# OpenPilot_Atom.net
KiCad netlist of a schematic drawn in Altium Designer
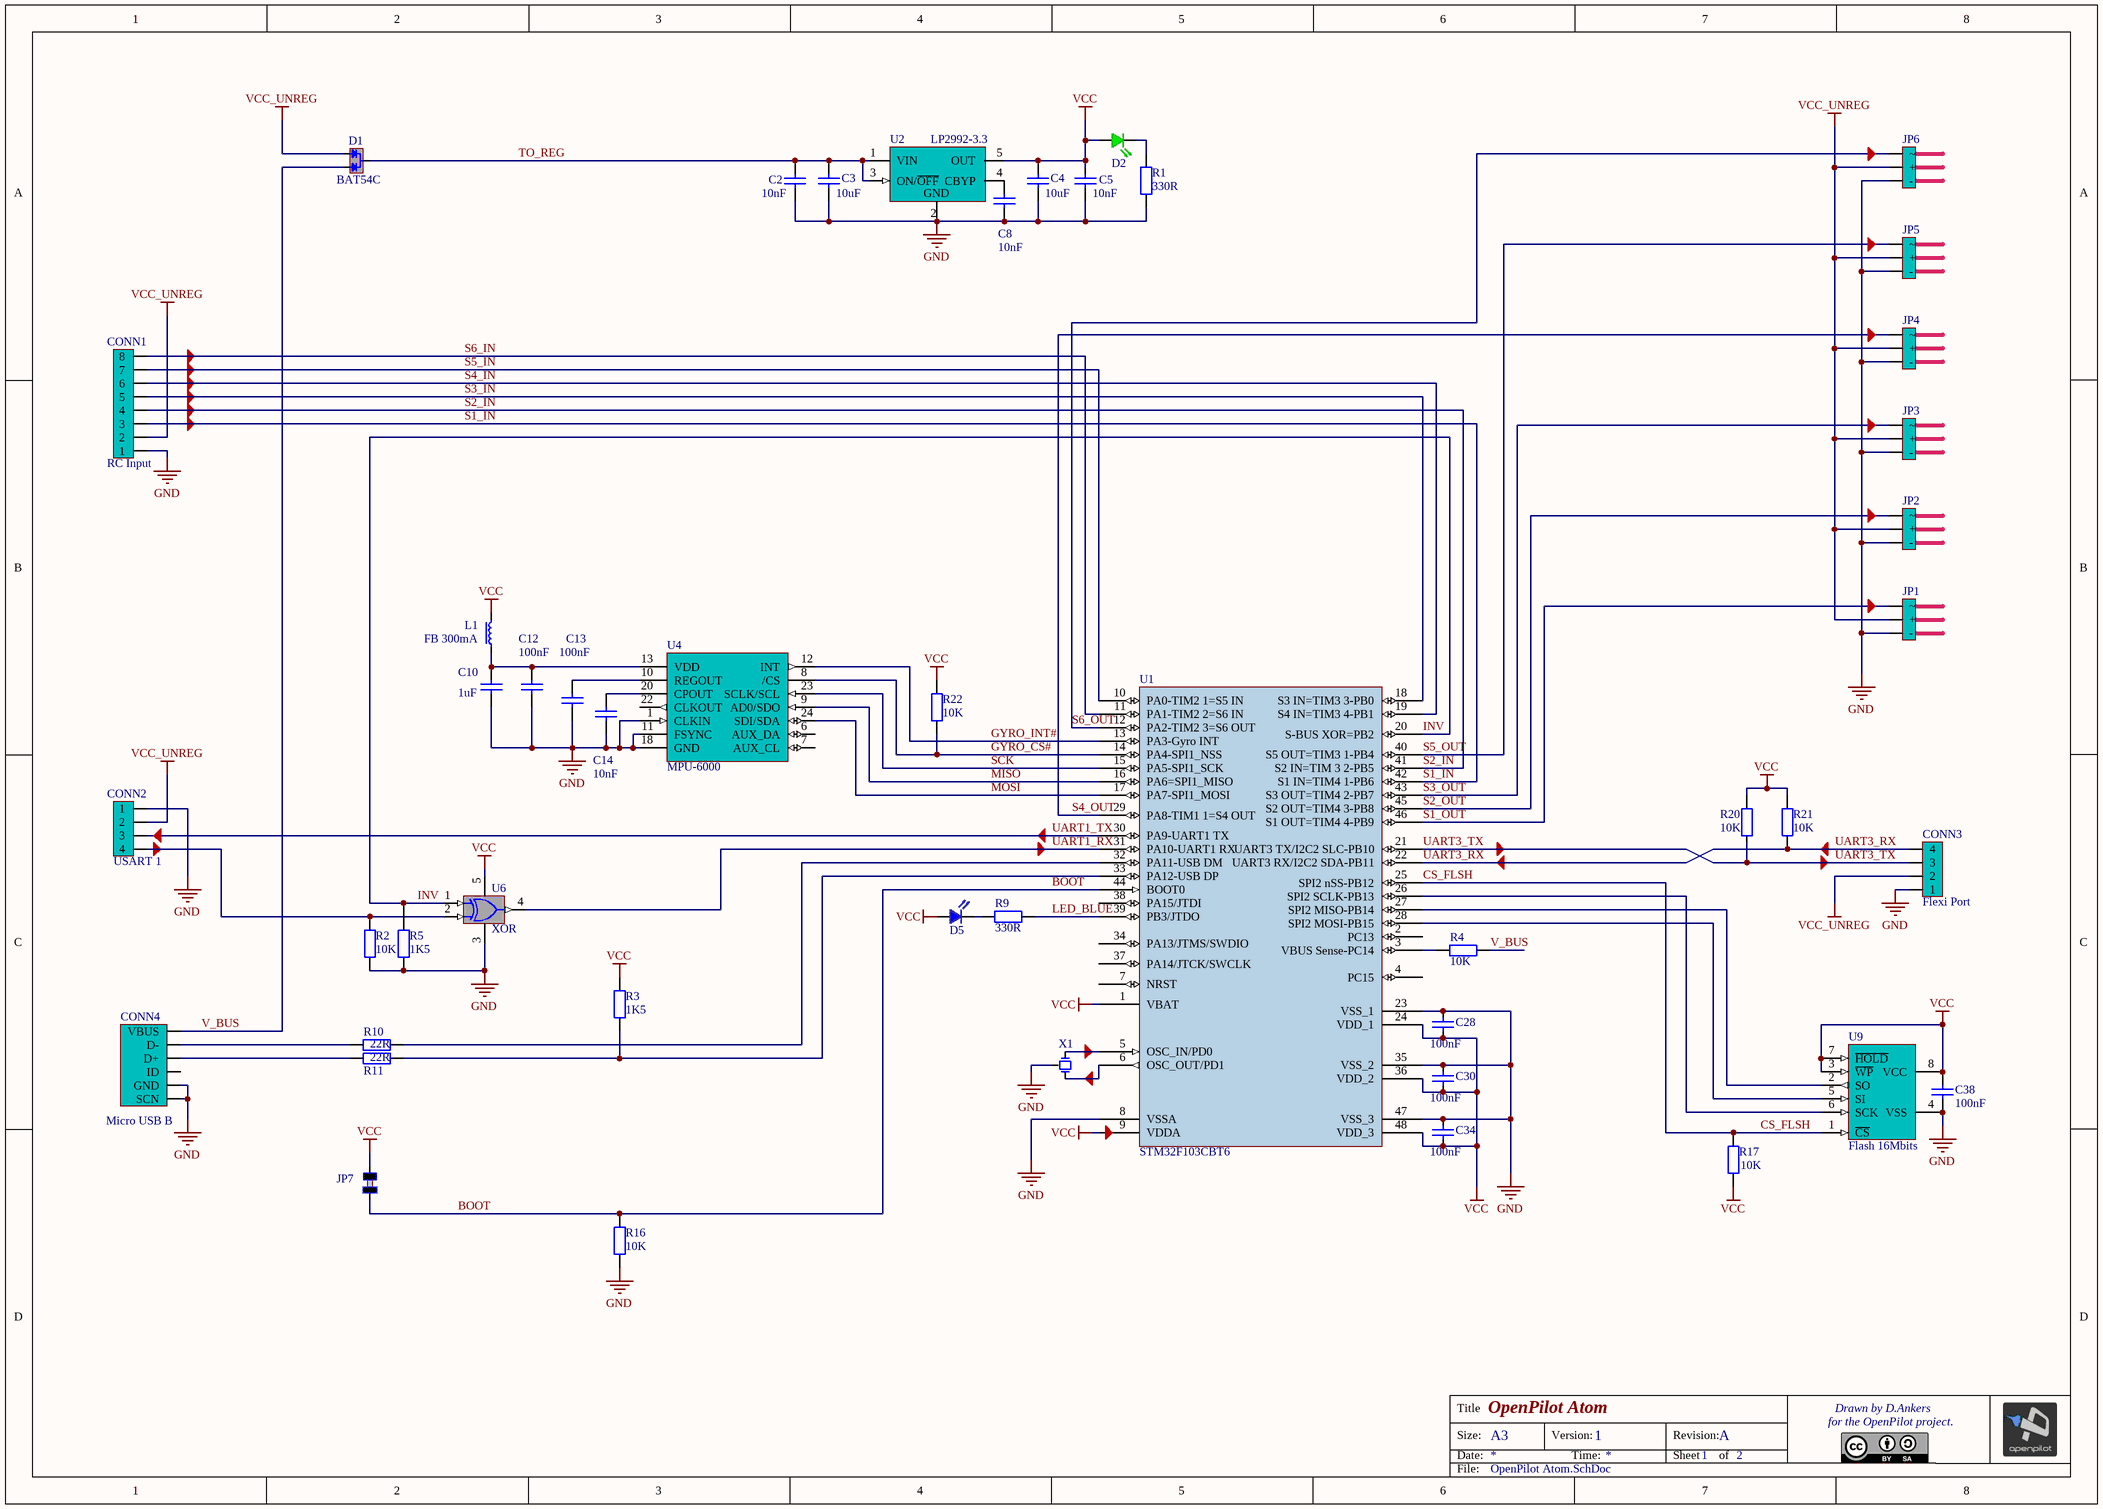
[diagram p0: OpenPilot Atom.SchDoc]

(export (version "E")
  (design (tool "Eeschema 10.0.6"))
  (components
    (comp (ref "C2")
      (value "10nF")
      (footprint "CAP402N")
      (description "Capacitor SMD")
      (fields (field (name "Comment") "10n") (field (name "PUBLISHER") "The OpenPilot Project"))
      (libsource (lib "") (part "Cap402_1"))
    )
    (comp (ref "C3")
      (value "10uF")
      (footprint "CAP805L")
      (description "Capacitor SMD")
      (fields (field (name "Comment") "Cap805") (field (name "PUBLISHER") "The OpenPilot Project"))
      (libsource (lib "OpenPilot") (part "Cap805"))
    )
    (comp (ref "C4")
      (value "10uF")
      (footprint "CAP805L")
      (description "Capacitor SMD")
      (fields (field (name "Comment") "Cap805") (field (name "PUBLISHER") "The OpenPilot Project"))
      (libsource (lib "OpenPilot") (part "Cap805"))
    )
    (comp (ref "C5")
      (value "10nF")
      (footprint "CAP402N")
      (description "Capacitor SMD")
      (fields (field (name "Comment") "10n") (field (name "PUBLISHER") "The OpenPilot Project"))
      (libsource (lib "") (part "Cap402_1"))
    )
    (comp (ref "C8")
      (value "10nF")
      (footprint "CAP402N")
      (description "Capacitor SMD")
      (fields (field (name "Comment") "10n") (field (name "PUBLISHER") "The OpenPilot Project"))
      (libsource (lib "") (part "Cap402_1"))
    )
    (comp (ref "C10")
      (value "1uF")
      (footprint "CAP402N")
      (description "Capacitor SMD")
      (fields (field (name "PUBLISHER") "The OpenPilot Project"))
      (libsource (lib "") (part "Cap402_1"))
    )
    (comp (ref "C12")
      (value "100nF")
      (footprint "CAP402N")
      (description "Capacitor SMD")
      (fields (field (name "Comment") "Cap402") (field (name "PUBLISHER") "The OpenPilot Project"))
      (libsource (lib "") (part "Cap402_1"))
    )
    (comp (ref "C13")
      (value "100nF")
      (footprint "CAP402N")
      (description "Capacitor SMD")
      (fields (field (name "Comment") "Cap402") (field (name "PUBLISHER") "The OpenPilot Project"))
      (libsource (lib "") (part "Cap402_1"))
    )
    (comp (ref "C14")
      (value "10nF")
      (footprint "CAP402N")
      (description "Capacitor SMD")
      (fields (field (name "Comment") "10n") (field (name "PUBLISHER") "The OpenPilot Project"))
      (libsource (lib "") (part "Cap402_1"))
    )
    (comp (ref "C28")
      (value "100nF")
      (footprint "CAP402N")
      (description "Capacitor SMD")
      (fields (field (name "Comment") "Cap402") (field (name "PUBLISHER") "The OpenPilot Project"))
      (libsource (lib "OpenPilot") (part "Cap402"))
    )
    (comp (ref "C30")
      (value "100nF")
      (footprint "CAP402N")
      (description "Capacitor SMD")
      (fields (field (name "Comment") "Cap402") (field (name "PUBLISHER") "The OpenPilot Project"))
      (libsource (lib "OpenPilot") (part "Cap402"))
    )
    (comp (ref "C34")
      (value "100nF")
      (footprint "CAP402N")
      (description "Capacitor SMD")
      (fields (field (name "Comment") "Cap402") (field (name "PUBLISHER") "The OpenPilot Project"))
      (libsource (lib "OpenPilot") (part "Cap402"))
    )
    (comp (ref "C38")
      (value "100nF")
      (footprint "CAP402N")
      (description "Capacitor SMD")
      (fields (field (name "Comment") "Cap402") (field (name "PUBLISHER") "The OpenPilot Project"))
      (libsource (lib "") (part "Cap402_1"))
    )
    (comp (ref "CONN1")
      (value "RC Input")
      (footprint "JST SH 8 Pin Side Entry")
      (description "JST-SH 8-pin Side Entry Socket")
      (fields (field (name "MANUFACTURER") "Generic Components"))
      (libsource (lib "OpenPilot") (part "JST-SH 8-pin Side Entry Socket"))
    )
    (comp (ref "CONN2")
      (value "USART 1")
      (footprint "JST SH 4 Pin Side Entry")
      (description "JST-SH 4-pin Side Entry Socket")
      (fields (field (name "MANUFACTURER") "Generic Components"))
      (libsource (lib "OpenPilot") (part "JST-SH 4-pin Side Entry Socket"))
    )
    (comp (ref "CONN3")
      (value "Flexi Port")
      (footprint "JST SH 4 Pin Side Entry")
      (description "JST-SH 4-pin Side Entry Socket")
      (fields (field (name "MANUFACTURER") "Generic Components"))
      (libsource (lib "") (part "JST-SH 4-pin Side Entry Socket_1"))
    )
    (comp (ref "CONN4")
      (value "Micro USB B")
      (footprint "Micro_USB")
      (description "USB Micro B SMT Socket")
      (fields (field (name "PUBLISHER") "The OpenPilot Project"))
      (libsource (lib "OpenPilot") (part "USB Micro B SMT"))
    )
    (comp (ref "D1")
      (value "BAT54C")
      (footprint "SOT23-3N")
      (description "Dual Diode Command Cathode")
      (libsource (lib "OpenPilot") (part "BAT54C"))
    )
    (comp (ref "D2")
      (value "Green")
      (footprint "LED603N")
      (description "Green 603 LED")
      (libsource (lib "OpenPilot") (part "LED 603 Gr"))
    )
    (comp (ref "D5")
      (value "Blue")
      (footprint "LED603N")
      (description "Blue 603 LED")
      (libsource (lib "OpenPilot") (part "LED 603 Bl"))
    )
    (comp (ref "JP1")
      (value "Servo out 1")
      (footprint "SIP3 - 0.1")
      (description "Header, 3-Pin, 0.1\"")
      (fields (field (name "MANUFACTURER") "Generic Components"))
      (libsource (lib "OpenPilot") (part "Hdr 3 Pin 0.1"))
    )
    (comp (ref "JP2")
      (value "Servo out 2")
      (footprint "SIP3 - 0.1")
      (description "Header, 3-Pin, 0.1\"")
      (fields (field (name "MANUFACTURER") "Generic Components"))
      (libsource (lib "OpenPilot") (part "Hdr 3 Pin 0.1"))
    )
    (comp (ref "JP3")
      (value "Servo out 3")
      (footprint "SIP3 - 0.1")
      (description "Header, 3-Pin, 0.1\"")
      (fields (field (name "MANUFACTURER") "Generic Components"))
      (libsource (lib "OpenPilot") (part "Hdr 3 Pin 0.1"))
    )
    (comp (ref "JP4")
      (value "Servo out 4")
      (footprint "SIP3 - 0.1")
      (description "Header, 3-Pin, 0.1\"")
      (fields (field (name "MANUFACTURER") "Generic Components"))
      (libsource (lib "OpenPilot") (part "Hdr 3 Pin 0.1"))
    )
    (comp (ref "JP5")
      (value "Servo out 5")
      (footprint "SIP3 - 0.1")
      (description "Header, 3-Pin, 0.1\"")
      (fields (field (name "MANUFACTURER") "Generic Components"))
      (libsource (lib "OpenPilot") (part "Hdr 3 Pin 0.1"))
    )
    (comp (ref "JP6")
      (value "Servo out 6")
      (footprint "SIP3 - 0.1")
      (description "Header, 3-Pin, 0.1\"")
      (fields (field (name "MANUFACTURER") "Generic Components"))
      (libsource (lib "OpenPilot") (part "Hdr 3 Pin 0.1"))
    )
    (comp (ref "JP7")
      (value "2 PAD Touch JMP")
      (footprint "TOUCH JMP 2PAD")
      (description "2 Pad Touch Jumper")
      (fields (field (name "PUBLISHER") "The OpenPilot Project"))
      (libsource (lib "OpenPilot") (part "2 PAD Touch JMP"))
    )
    (comp (ref "L1")
      (value "FB 300mA")
      (footprint "IND603N")
      (description "Ferrite Bead 300mA")
      (fields (field (name "MANUFACTURER") "Generic Components"))
      (libsource (lib "OpenPilot") (part "FerriteBead_300mA"))
    )
    (comp (ref "R1")
      (value "330R")
      (footprint "RES402N")
      (description "Resistor SMD")
      (fields (field (name "Comment") "Res402") (field (name "PUBLISHER") "The OpenPilot Project"))
      (libsource (lib "") (part "Res402_1"))
    )
    (comp (ref "R2")
      (value "10K")
      (footprint "RES402N")
      (description "Resistor SMD")
      (fields (field (name "Comment") "Res402") (field (name "PUBLISHER") "The OpenPilot Project"))
      (libsource (lib "") (part "Res402_1"))
    )
    (comp (ref "R3")
      (value "1K5")
      (footprint "RES402N")
      (description "Resistor SMD")
      (fields (field (name "Comment") "Res402") (field (name "PUBLISHER") "The OpenPilot Project"))
      (libsource (lib "") (part "Res402_1"))
    )
    (comp (ref "R4")
      (value "10K")
      (footprint "RES402N")
      (description "Resistor SMD")
      (fields (field (name "Comment") "Res402") (field (name "PUBLISHER") "The OpenPilot Project"))
      (libsource (lib "OpenPilot") (part "Res402"))
    )
    (comp (ref "R5")
      (value "1K5")
      (footprint "RES402N")
      (description "Resistor SMD")
      (fields (field (name "Comment") "Res402") (field (name "PUBLISHER") "The OpenPilot Project"))
      (libsource (lib "") (part "Res402_4"))
    )
    (comp (ref "R9")
      (value "330R")
      (footprint "RES402N")
      (description "Resistor SMD")
      (fields (field (name "Comment") "Res402") (field (name "PUBLISHER") "The OpenPilot Project"))
      (libsource (lib "") (part "Res402_3"))
    )
    (comp (ref "R10")
      (value "22R")
      (footprint "RES402N")
      (description "Resistor SMD")
      (fields (field (name "Comment") "Res402") (field (name "PUBLISHER") "The OpenPilot Project"))
      (libsource (lib "OpenPilot") (part "Res402"))
    )
    (comp (ref "R11")
      (value "22R")
      (footprint "RES402N")
      (description "Resistor SMD")
      (fields (field (name "Comment") "Res402") (field (name "PUBLISHER") "The OpenPilot Project"))
      (libsource (lib "OpenPilot") (part "Res402"))
    )
    (comp (ref "R16")
      (value "10K")
      (footprint "RES402N")
      (description "Resistor SMD")
      (fields (field (name "Comment") "Res402") (field (name "PUBLISHER") "The OpenPilot Project"))
      (libsource (lib "") (part "Res402_1"))
    )
    (comp (ref "R17")
      (value "10K")
      (footprint "RES402N")
      (description "Resistor SMD")
      (fields (field (name "Comment") "Res402") (field (name "PUBLISHER") "The OpenPilot Project"))
      (libsource (lib "") (part "Res402_1"))
    )
    (comp (ref "R20")
      (value "10K")
      (footprint "RES402N")
      (description "Resistor SMD")
      (fields (field (name "Comment") "Res402") (field (name "PUBLISHER") "The OpenPilot Project"))
      (libsource (lib "") (part "Res402_2"))
    )
    (comp (ref "R21")
      (value "10K")
      (footprint "RES402N")
      (description "Resistor SMD")
      (fields (field (name "Comment") "Res402") (field (name "PUBLISHER") "The OpenPilot Project"))
      (libsource (lib "") (part "Res402_1"))
    )
    (comp (ref "R22")
      (value "10K")
      (footprint "RES402N")
      (description "Resistor SMD")
      (fields (field (name "Comment") "Res402") (field (name "PUBLISHER") "The OpenPilot Project"))
      (libsource (lib "") (part "Res402_1"))
    )
    (comp (ref "U1")
      (value "STM32F103CBT6")
      (footprint "STM32 48 Lead")
      (description "STM32 ARM-based 32-bit MCU with 128 Kbytes Flash, 48-pin LQFP, Industrial Temperature")
      (fields (field (name "PUBLISHER") "Altium Limited"))
      (libsource (lib "OpenPilot") (part "STM32F103CBT6"))
    )
    (comp (ref "U2")
      (value "LP2992-3.3")
      (footprint "SOT23-5L")
      (description "3.3V 250mA LDO Regulator")
      (libsource (lib "OpenPilot") (part "LP2985-3.3"))
    )
    (comp (ref "U4")
      (value "MPU-6000")
      (footprint "IMU-3000")
      (description "Invensense MPU-3/6000,  3-axis Gyros & Accel on 6000")
      (fields (field (name "MANUFACTURER") "Invensense") (field (name "PUBLISHER") "The OpenPilot Project"))
      (libsource (lib "OpenPilot") (part "MPU-3/6000"))
    )
    (comp (ref "U6")
      (value "XOR")
      (footprint "DCK-5")
      (description "XOR Gate SN74LVC1G86DCKR")
      (libsource (lib "OpenPilot") (part "XOR SN74LVC1G86DCKR"))
    )
    (comp (ref "U9")
      (value "Flash 16Mbits")
      (footprint "SOIC8_N")
      (description "16Mbit SPI Flash Memory")
      (fields (field (name "PUBLISHER") "The OpenPilot Project"))
      (libsource (lib "OpenPilot") (part "Flash 16Mb 75MHZ 8SOIC"))
    )
    (comp (ref "X1")
      (value "8Mhz Ceralock")
      (footprint "CERALOCK 8Mhz")
      (description "Ceralock 8Mhz with caps")
      (fields (field (name "PUBLISHER") "The OpenPilot Project"))
      (libsource (lib "OpenPilot") (part "CERALOCK8"))
    )
  )
  (nets
    (net (code "1") (name "/BOOT") (class "Default")
      (node (ref "JP7") (pin "1") (pinfunction "1_1") (pintype "passive"))
      (node (ref "R16") (pin "2") (pinfunction "2_2") (pintype "passive"))
      (node (ref "U1") (pin "44") (pinfunction "BOOT0_44") (pintype "input"))
    )
    (net (code "2") (name "/CS_FLSH") (class "Default")
      (node (ref "R17") (pin "2") (pinfunction "2_2") (pintype "passive"))
      (node (ref "U1") (pin "25") (pinfunction "SPI2_nSS-PB12_25") (pintype "bidirectional"))
      (node (ref "U9") (pin "1") (pinfunction "~{CS}_1") (pintype "input"))
    )
    (net (code "3") (name "/GYRO_CS#") (class "Default")
      (node (ref "R22") (pin "1") (pinfunction "1_1") (pintype "passive"))
      (node (ref "U1") (pin "14") (pinfunction "PA4-SPI1_NSS_14") (pintype "bidirectional"))
      (node (ref "U4") (pin "8") (pinfunction "/CS_8") (pintype "passive"))
    )
    (net (code "4") (name "/GYRO_INT#") (class "Default")
      (node (ref "U1") (pin "13") (pinfunction "PA3-Gyro_INT_13") (pintype "bidirectional"))
      (node (ref "U4") (pin "12") (pinfunction "INT_12") (pintype "output"))
    )
    (net (code "5") (name "/INV") (class "Default")
      (node (ref "R5") (pin "2") (pinfunction "2_2") (pintype "passive"))
      (node (ref "U1") (pin "20") (pinfunction "S-BUS_XOR=PB2_20") (pintype "bidirectional"))
      (node (ref "U6") (pin "1") (pinfunction "A_1") (pintype "input"))
    )
    (net (code "6") (name "/LED_BLUE") (class "Default")
      (node (ref "R9") (pin "2") (pinfunction "2_2") (pintype "passive"))
      (node (ref "U1") (pin "39") (pinfunction "PB3/JTDO_39") (pintype "bidirectional"))
    )
    (net (code "7") (name "/MISO") (class "Default")
      (node (ref "U1") (pin "16") (pinfunction "PA6=SPI1_MISO_16") (pintype "bidirectional"))
      (node (ref "U4") (pin "9") (pinfunction "AD0/SDO_9") (pintype "input"))
    )
    (net (code "8") (name "/MOSI") (class "Default")
      (node (ref "U1") (pin "17") (pinfunction "PA7-SPI1_MOSI_17") (pintype "bidirectional"))
      (node (ref "U4") (pin "24") (pinfunction "SDI/SDA_24") (pintype "bidirectional"))
    )
    (net (code "9") (name "/S1_IN") (class "Default")
      (node (ref "CONN1") (pin "3") (pinfunction "3_3") (pintype "passive"))
      (node (ref "U1") (pin "42") (pinfunction "S1_IN=TIM4_1-PB6_42") (pintype "bidirectional"))
    )
    (net (code "10") (name "/S1_OUT") (class "Default")
      (node (ref "JP1") (pin "1") (pinfunction "~_1") (pintype "passive"))
      (node (ref "U1") (pin "46") (pinfunction "S1_OUT=TIM4_4-PB9_46") (pintype "bidirectional"))
    )
    (net (code "11") (name "/S2_IN") (class "Default")
      (node (ref "CONN1") (pin "4") (pinfunction "4_4") (pintype "passive"))
      (node (ref "U1") (pin "41") (pinfunction "S2_IN=TIM_3_2-PB5_41") (pintype "bidirectional"))
    )
    (net (code "12") (name "/S2_OUT") (class "Default")
      (node (ref "JP2") (pin "1") (pinfunction "~_1") (pintype "passive"))
      (node (ref "U1") (pin "45") (pinfunction "S2_OUT=TIM4_3-PB8_45") (pintype "bidirectional"))
    )
    (net (code "13") (name "/S3_IN") (class "Default")
      (node (ref "CONN1") (pin "5") (pinfunction "5_5") (pintype "passive"))
      (node (ref "U1") (pin "18") (pinfunction "S3_IN=TIM3_3-PB0_18") (pintype "bidirectional"))
    )
    (net (code "14") (name "/S3_OUT") (class "Default")
      (node (ref "JP3") (pin "1") (pinfunction "~_1") (pintype "passive"))
      (node (ref "U1") (pin "43") (pinfunction "S3_OUT=TIM4_2-PB7_43") (pintype "bidirectional"))
    )
    (net (code "15") (name "/S4_IN") (class "Default")
      (node (ref "CONN1") (pin "6") (pinfunction "6_6") (pintype "passive"))
      (node (ref "U1") (pin "19") (pinfunction "S4_IN=TIM3_4-PB1_19") (pintype "bidirectional"))
    )
    (net (code "16") (name "/S4_OUT") (class "Default")
      (node (ref "JP4") (pin "1") (pinfunction "~_1") (pintype "passive"))
      (node (ref "U1") (pin "29") (pinfunction "PA8-TIM1_1=S4_OUT_29") (pintype "bidirectional"))
    )
    (net (code "17") (name "/S5_IN") (class "Default")
      (node (ref "CONN1") (pin "7") (pinfunction "7_7") (pintype "passive"))
      (node (ref "U1") (pin "10") (pinfunction "PA0-TIM2_1=S5_IN_10") (pintype "bidirectional"))
    )
    (net (code "18") (name "/S5_OUT") (class "Default")
      (node (ref "JP5") (pin "1") (pinfunction "~_1") (pintype "passive"))
      (node (ref "U1") (pin "40") (pinfunction "S5_OUT=TIM3_1-PB4_40") (pintype "bidirectional"))
    )
    (net (code "19") (name "/S6_IN") (class "Default")
      (node (ref "CONN1") (pin "8") (pinfunction "8_8") (pintype "passive"))
      (node (ref "U1") (pin "11") (pinfunction "PA1-TIM2_2=S6_IN_11") (pintype "bidirectional"))
    )
    (net (code "20") (name "/S6_OUT") (class "Default")
      (node (ref "JP6") (pin "1") (pinfunction "~_1") (pintype "passive"))
      (node (ref "U1") (pin "12") (pinfunction "PA2-TIM2_3=S6_OUT_12") (pintype "bidirectional"))
    )
    (net (code "21") (name "/SCK") (class "Default")
      (node (ref "U1") (pin "15") (pinfunction "PA5-SPI1_SCK_15") (pintype "bidirectional"))
      (node (ref "U4") (pin "23") (pinfunction "SCLK/SCL_23") (pintype "input"))
    )
    (net (code "22") (name "/TO_REG") (class "Default")
      (node (ref "C2") (pin "1") (pinfunction "1_1") (pintype "passive"))
      (node (ref "C3") (pin "1") (pinfunction "1_1") (pintype "passive"))
      (node (ref "D1") (pin "3") (pinfunction "COM_3") (pintype "passive"))
      (node (ref "U2") (pin "1") (pinfunction "VIN_1") (pintype "power_in"))
      (node (ref "U2") (pin "3") (pinfunction "ON/~{OFF}_3") (pintype "input"))
    )
    (net (code "23") (name "/UART1_RX") (class "Default")
      (node (ref "U1") (pin "31") (pinfunction "PA10-UART1_RX_31") (pintype "bidirectional"))
      (node (ref "U6") (pin "4") (pinfunction "Y_4") (pintype "output"))
    )
    (net (code "24") (name "/UART1_TX") (class "Default")
      (node (ref "CONN2") (pin "3") (pinfunction "3_3") (pintype "passive"))
      (node (ref "U1") (pin "30") (pinfunction "PA9-UART1_TX_30") (pintype "bidirectional"))
    )
    (net (code "25") (name "/UART3_RX") (class "Default")
      (node (ref "CONN3") (pin "4") (pinfunction "4_4") (pintype "passive"))
      (node (ref "R21") (pin "1") (pinfunction "1_1") (pintype "passive"))
      (node (ref "U1") (pin "22") (pinfunction "UART3_RX/I2C2_SDA-PB11_22") (pintype "bidirectional"))
    )
    (net (code "26") (name "/UART3_TX") (class "Default")
      (node (ref "CONN3") (pin "3") (pinfunction "3_3") (pintype "passive"))
      (node (ref "R20") (pin "1") (pinfunction "1_1") (pintype "passive"))
      (node (ref "U1") (pin "21") (pinfunction "UART3_TX/I2C2_SLC-PB10_21") (pintype "bidirectional"))
    )
    (net (code "27") (name "/V_BUS") (class "Default")
      (node (ref "CONN4") (pin "1") (pinfunction "VBUS_1") (pintype "passive"))
      (node (ref "D1") (pin "2") (pinfunction "A2_2") (pintype "passive"))
      (node (ref "R4") (pin "1") (pinfunction "1_1") (pintype "passive"))
    )
    (net (code "28") (name "GND") (class "Default")
      (node (ref "C10") (pin "2") (pinfunction "2_2") (pintype "passive"))
      (node (ref "C12") (pin "2") (pinfunction "2_2") (pintype "passive"))
      (node (ref "C13") (pin "2") (pinfunction "2_2") (pintype "passive"))
      (node (ref "C14") (pin "1") (pinfunction "1_1") (pintype "passive"))
      (node (ref "C2") (pin "2") (pinfunction "2_2") (pintype "passive"))
      (node (ref "C28") (pin "1") (pinfunction "1_1") (pintype "passive"))
      (node (ref "C3") (pin "2") (pinfunction "2_2") (pintype "passive"))
      (node (ref "C30") (pin "1") (pinfunction "1_1") (pintype "passive"))
      (node (ref "C34") (pin "1") (pinfunction "1_1") (pintype "passive"))
      (node (ref "C38") (pin "2") (pinfunction "2_2") (pintype "passive"))
      (node (ref "C4") (pin "2") (pinfunction "2_2") (pintype "passive"))
      (node (ref "C5") (pin "2") (pinfunction "2_2") (pintype "passive"))
      (node (ref "C8") (pin "2") (pinfunction "2_2") (pintype "passive"))
      (node (ref "CONN1") (pin "1") (pinfunction "1_1") (pintype "passive"))
      (node (ref "CONN2") (pin "1") (pinfunction "1_1") (pintype "passive"))
      (node (ref "CONN3") (pin "1") (pinfunction "1_1") (pintype "passive"))
      (node (ref "CONN4") (pin "0") (pinfunction "SCN_0") (pintype "passive"))
      (node (ref "CONN4") (pin "5") (pinfunction "GND_5") (pintype "passive"))
      (node (ref "JP1") (pin "3") (pinfunction "-_3") (pintype "passive"))
      (node (ref "JP2") (pin "3") (pinfunction "-_3") (pintype "passive"))
      (node (ref "JP3") (pin "3") (pinfunction "-_3") (pintype "passive"))
      (node (ref "JP4") (pin "3") (pinfunction "-_3") (pintype "passive"))
      (node (ref "JP5") (pin "3") (pinfunction "-_3") (pintype "passive"))
      (node (ref "JP6") (pin "3") (pinfunction "-_3") (pintype "passive"))
      (node (ref "R1") (pin "1") (pinfunction "1_1") (pintype "passive"))
      (node (ref "R16") (pin "1") (pinfunction "1_1") (pintype "passive"))
      (node (ref "R2") (pin "1") (pinfunction "1_1") (pintype "passive"))
      (node (ref "R5") (pin "1") (pinfunction "1_1") (pintype "passive"))
      (node (ref "U1") (pin "23") (pinfunction "VSS_1_23") (pintype "power_in"))
      (node (ref "U1") (pin "35") (pinfunction "VSS_2_35") (pintype "power_in"))
      (node (ref "U1") (pin "47") (pinfunction "VSS_3_47") (pintype "power_in"))
      (node (ref "U1") (pin "8") (pinfunction "VSSA_8") (pintype "power_in"))
      (node (ref "U2") (pin "2") (pinfunction "GND_2") (pintype "power_in"))
      (node (ref "U4") (pin "1") (pinfunction "CLKIN_1") (pintype "input"))
      (node (ref "U4") (pin "11") (pinfunction "FSYNC_11") (pintype "passive"))
      (node (ref "U4") (pin "18") (pinfunction "GND_18") (pintype "power_in"))
      (node (ref "U6") (pin "3") (pinfunction "GND_3") (pintype "power_in"))
      (node (ref "U9") (pin "4") (pinfunction "VSS_4") (pintype "power_in"))
      (node (ref "X1") (pin "3") (pinfunction "3_3") (pintype "passive"))
    )
    (net (code "29") (name "Net-(CONN4-D+)") (class "Default")
      (node (ref "CONN4") (pin "3") (pinfunction "D+_3") (pintype "passive"))
      (node (ref "R11") (pin "2") (pinfunction "2_2") (pintype "passive"))
    )
    (net (code "30") (name "Net-(CONN4-D-)") (class "Default")
      (node (ref "CONN4") (pin "2") (pinfunction "D-_2") (pintype "passive"))
      (node (ref "R10") (pin "2") (pinfunction "2_2") (pintype "passive"))
    )
    (net (code "31") (name "Net-(D2-K)") (class "Default")
      (node (ref "D2") (pin "1") (pinfunction "K_1") (pintype "passive"))
      (node (ref "R1") (pin "2") (pinfunction "2_2") (pintype "passive"))
    )
    (net (code "32") (name "Net-(D5-K)") (class "Default")
      (node (ref "D5") (pin "1") (pinfunction "K_1") (pintype "passive"))
      (node (ref "R9") (pin "1") (pinfunction "1_1") (pintype "passive"))
    )
    (net (code "33") (name "Net-(U1-OSC_IN{slash}PD0)") (class "Default")
      (node (ref "U1") (pin "5") (pinfunction "OSC_IN/PD0_5") (pintype "input"))
      (node (ref "X1") (pin "1") (pinfunction "1_1") (pintype "passive"))
    )
    (net (code "34") (name "Net-(U1-OSC_OUT{slash}PD1)") (class "Default")
      (node (ref "U1") (pin "6") (pinfunction "OSC_OUT/PD1_6") (pintype "output"))
      (node (ref "X1") (pin "2") (pinfunction "2_2") (pintype "passive"))
    )
    (net (code "35") (name "Net-(U1-PA11-USB_DM)") (class "Default")
      (node (ref "R10") (pin "1") (pinfunction "1_1") (pintype "passive"))
      (node (ref "U1") (pin "32") (pinfunction "PA11-USB_DM_32") (pintype "bidirectional"))
    )
    (net (code "36") (name "Net-(U1-PA12-USB_DP)") (class "Default")
      (node (ref "R11") (pin "1") (pinfunction "1_1") (pintype "passive"))
      (node (ref "R3") (pin "1") (pinfunction "1_1") (pintype "passive"))
      (node (ref "U1") (pin "33") (pinfunction "PA12-USB_DP_33") (pintype "bidirectional"))
    )
    (net (code "37") (name "Net-(U1-SPI2_MISO-PB14)") (class "Default")
      (node (ref "U1") (pin "27") (pinfunction "SPI2_MISO-PB14_27") (pintype "bidirectional"))
      (node (ref "U9") (pin "2") (pinfunction "SO_2") (pintype "output"))
    )
    (net (code "38") (name "Net-(U1-SPI2_MOSI-PB15)") (class "Default")
      (node (ref "U1") (pin "28") (pinfunction "SPI2_MOSI-PB15_28") (pintype "bidirectional"))
      (node (ref "U9") (pin "5") (pinfunction "SI_5") (pintype "input"))
    )
    (net (code "39") (name "Net-(U1-SPI2_SCLK-PB13)") (class "Default")
      (node (ref "U1") (pin "26") (pinfunction "SPI2_SCLK-PB13_26") (pintype "bidirectional"))
      (node (ref "U9") (pin "6") (pinfunction "SCK_6") (pintype "input"))
    )
    (net (code "40") (name "Net-(U1-VBUS_Sense-PC14)") (class "Default")
      (node (ref "R4") (pin "2") (pinfunction "2_2") (pintype "passive"))
      (node (ref "U1") (pin "3") (pinfunction "VBUS_Sense-PC14_3") (pintype "bidirectional"))
    )
    (net (code "41") (name "Net-(U2-CBYP)") (class "Default")
      (node (ref "C8") (pin "1") (pinfunction "1_1") (pintype "passive"))
      (node (ref "U2") (pin "4") (pinfunction "CBYP_4") (pintype "passive"))
    )
    (net (code "42") (name "Net-(U4-CPOUT)") (class "Default")
      (node (ref "C14") (pin "2") (pinfunction "2_2") (pintype "passive"))
      (node (ref "U4") (pin "20") (pinfunction "CPOUT_20") (pintype "passive"))
    )
    (net (code "43") (name "Net-(U4-REGOUT)") (class "Default")
      (node (ref "C13") (pin "1") (pinfunction "1_1") (pintype "passive"))
      (node (ref "U4") (pin "10") (pinfunction "REGOUT_10") (pintype "passive"))
    )
    (net (code "44") (name "Net-(U4-VDD)") (class "Default")
      (node (ref "C10") (pin "1") (pinfunction "1_1") (pintype "passive"))
      (node (ref "C12") (pin "1") (pinfunction "1_1") (pintype "passive"))
      (node (ref "L1") (pin "1") (pinfunction "1_1") (pintype "passive"))
      (node (ref "U4") (pin "13") (pinfunction "VDD_13") (pintype "power_in"))
    )
    (net (code "45") (name "Net-(U6-B)") (class "Default")
      (node (ref "CONN2") (pin "4") (pinfunction "4_4") (pintype "passive"))
      (node (ref "R2") (pin "2") (pinfunction "2_2") (pintype "passive"))
      (node (ref "U6") (pin "2") (pinfunction "B_2") (pintype "input"))
    )
    (net (code "46") (name "VCC") (class "Default")
      (node (ref "C28") (pin "2") (pinfunction "2_2") (pintype "passive"))
      (node (ref "C30") (pin "2") (pinfunction "2_2") (pintype "passive"))
      (node (ref "C34") (pin "2") (pinfunction "2_2") (pintype "passive"))
      (node (ref "C38") (pin "1") (pinfunction "1_1") (pintype "passive"))
      (node (ref "C4") (pin "1") (pinfunction "1_1") (pintype "passive"))
      (node (ref "C5") (pin "1") (pinfunction "1_1") (pintype "passive"))
      (node (ref "D2") (pin "2") (pinfunction "A_2") (pintype "passive"))
      (node (ref "D5") (pin "2") (pinfunction "A_2") (pintype "passive"))
      (node (ref "JP7") (pin "2") (pinfunction "2_2") (pintype "passive"))
      (node (ref "L1") (pin "2") (pinfunction "2_2") (pintype "passive"))
      (node (ref "R17") (pin "1") (pinfunction "1_1") (pintype "passive"))
      (node (ref "R20") (pin "2") (pinfunction "2_2") (pintype "passive"))
      (node (ref "R21") (pin "2") (pinfunction "2_2") (pintype "passive"))
      (node (ref "R22") (pin "2") (pinfunction "2_2") (pintype "passive"))
      (node (ref "R3") (pin "2") (pinfunction "2_2") (pintype "passive"))
      (node (ref "U1") (pin "1") (pinfunction "VBAT_1") (pintype "power_in"))
      (node (ref "U1") (pin "24") (pinfunction "VDD_1_24") (pintype "power_in"))
      (node (ref "U1") (pin "36") (pinfunction "VDD_2_36") (pintype "power_in"))
      (node (ref "U1") (pin "48") (pinfunction "VDD_3_48") (pintype "power_in"))
      (node (ref "U1") (pin "9") (pinfunction "VDDA_9") (pintype "power_in"))
      (node (ref "U2") (pin "5") (pinfunction "OUT_5") (pintype "power_in"))
      (node (ref "U6") (pin "5") (pinfunction "VCC_5") (pintype "power_in"))
      (node (ref "U9") (pin "3") (pinfunction "~{WP}_3") (pintype "input"))
      (node (ref "U9") (pin "7") (pinfunction "~{HOLD}_7") (pintype "input"))
      (node (ref "U9") (pin "8") (pinfunction "VCC_8") (pintype "power_in"))
    )
    (net (code "47") (name "VCC_UNREG") (class "Default")
      (node (ref "CONN1") (pin "2") (pinfunction "2_2") (pintype "passive"))
      (node (ref "CONN2") (pin "2") (pinfunction "2_2") (pintype "passive"))
      (node (ref "CONN3") (pin "2") (pinfunction "2_2") (pintype "passive"))
      (node (ref "D1") (pin "1") (pinfunction "A1_1") (pintype "passive"))
      (node (ref "JP1") (pin "2") (pinfunction "+_2") (pintype "passive"))
      (node (ref "JP2") (pin "2") (pinfunction "+_2") (pintype "passive"))
      (node (ref "JP3") (pin "2") (pinfunction "+_2") (pintype "passive"))
      (node (ref "JP4") (pin "2") (pinfunction "+_2") (pintype "passive"))
      (node (ref "JP5") (pin "2") (pinfunction "+_2") (pintype "passive"))
      (node (ref "JP6") (pin "2") (pinfunction "+_2") (pintype "passive"))
    )
    (net (code "48") (name "unconnected-(CONN4-ID-Pad4)") (class "Default")
      (node (ref "CONN4") (pin "4") (pinfunction "ID_4") (pintype "passive"))
    )
    (net (code "49") (name "unconnected-(U1-NRST-Pad7)") (class "Default")
      (node (ref "U1") (pin "7") (pinfunction "NRST_7") (pintype "bidirectional"))
    )
    (net (code "50") (name "unconnected-(U1-PA13{slash}JTMS{slash}SWDIO-Pad34)") (class "Default")
      (node (ref "U1") (pin "34") (pinfunction "PA13/JTMS/SWDIO_34") (pintype "bidirectional"))
    )
    (net (code "51") (name "unconnected-(U1-PA14{slash}JTCK{slash}SWCLK-Pad37)") (class "Default")
      (node (ref "U1") (pin "37") (pinfunction "PA14/JTCK/SWCLK_37") (pintype "bidirectional"))
    )
    (net (code "52") (name "unconnected-(U1-PA15{slash}JTDI-Pad38)") (class "Default")
      (node (ref "U1") (pin "38") (pinfunction "PA15/JTDI_38") (pintype "bidirectional"))
    )
    (net (code "53") (name "unconnected-(U1-PC13-Pad2)") (class "Default")
      (node (ref "U1") (pin "2") (pinfunction "PC13_2") (pintype "bidirectional"))
    )
    (net (code "54") (name "unconnected-(U1-PC15-Pad4)") (class "Default")
      (node (ref "U1") (pin "4") (pinfunction "PC15_4") (pintype "bidirectional"))
    )
    (net (code "55") (name "unconnected-(U4-AUX_CL-Pad7)") (class "Default")
      (node (ref "U4") (pin "7") (pinfunction "AUX_CL_7") (pintype "bidirectional"))
    )
    (net (code "56") (name "unconnected-(U4-AUX_DA-Pad6)") (class "Default")
      (node (ref "U4") (pin "6") (pinfunction "AUX_DA_6") (pintype "bidirectional"))
    )
    (net (code "57") (name "unconnected-(U4-CLKOUT-Pad22)") (class "Default")
      (node (ref "U4") (pin "22") (pinfunction "CLKOUT_22") (pintype "output"))
    )
    (net (code "58") (name "unconnected-(U4-NC-Pad2)") (class "Default")
      (node (ref "U4") (pin "2") (pinfunction "NC_2") (pintype "tri_state"))
    )
    (net (code "59") (name "unconnected-(U4-NC-Pad3)") (class "Default")
      (node (ref "U4") (pin "3") (pinfunction "NC_3") (pintype "tri_state"))
    )
    (net (code "60") (name "unconnected-(U4-NC-Pad4)") (class "Default")
      (node (ref "U4") (pin "4") (pinfunction "NC_4") (pintype "tri_state"))
    )
    (net (code "61") (name "unconnected-(U4-NC-Pad5)") (class "Default")
      (node (ref "U4") (pin "5") (pinfunction "NC_5") (pintype "tri_state"))
    )
    (net (code "62") (name "unconnected-(U4-NC-Pad14)") (class "Default")
      (node (ref "U4") (pin "14") (pinfunction "NC_14") (pintype "bidirectional"))
    )
    (net (code "63") (name "unconnected-(U4-NC-Pad15)") (class "Default")
      (node (ref "U4") (pin "15") (pinfunction "NC_15") (pintype "tri_state"))
    )
    (net (code "64") (name "unconnected-(U4-NC-Pad16)") (class "Default")
      (node (ref "U4") (pin "16") (pinfunction "NC_16") (pintype "tri_state"))
    )
    (net (code "65") (name "unconnected-(U4-NC-Pad17)") (class "Default")
      (node (ref "U4") (pin "17") (pinfunction "NC_17") (pintype "tri_state"))
    )
    (net (code "66") (name "unconnected-(U4-RESV-Pad19)") (class "Default")
      (node (ref "U4") (pin "19") (pinfunction "RESV_19") (pintype "passive"))
    )
    (net (code "67") (name "unconnected-(U4-RESV-Pad21)") (class "Default")
      (node (ref "U4") (pin "21") (pinfunction "RESV_21") (pintype "passive"))
    )
  )
)
